# relay.net
KiCad netlist of a schematic drawn in EAGLE
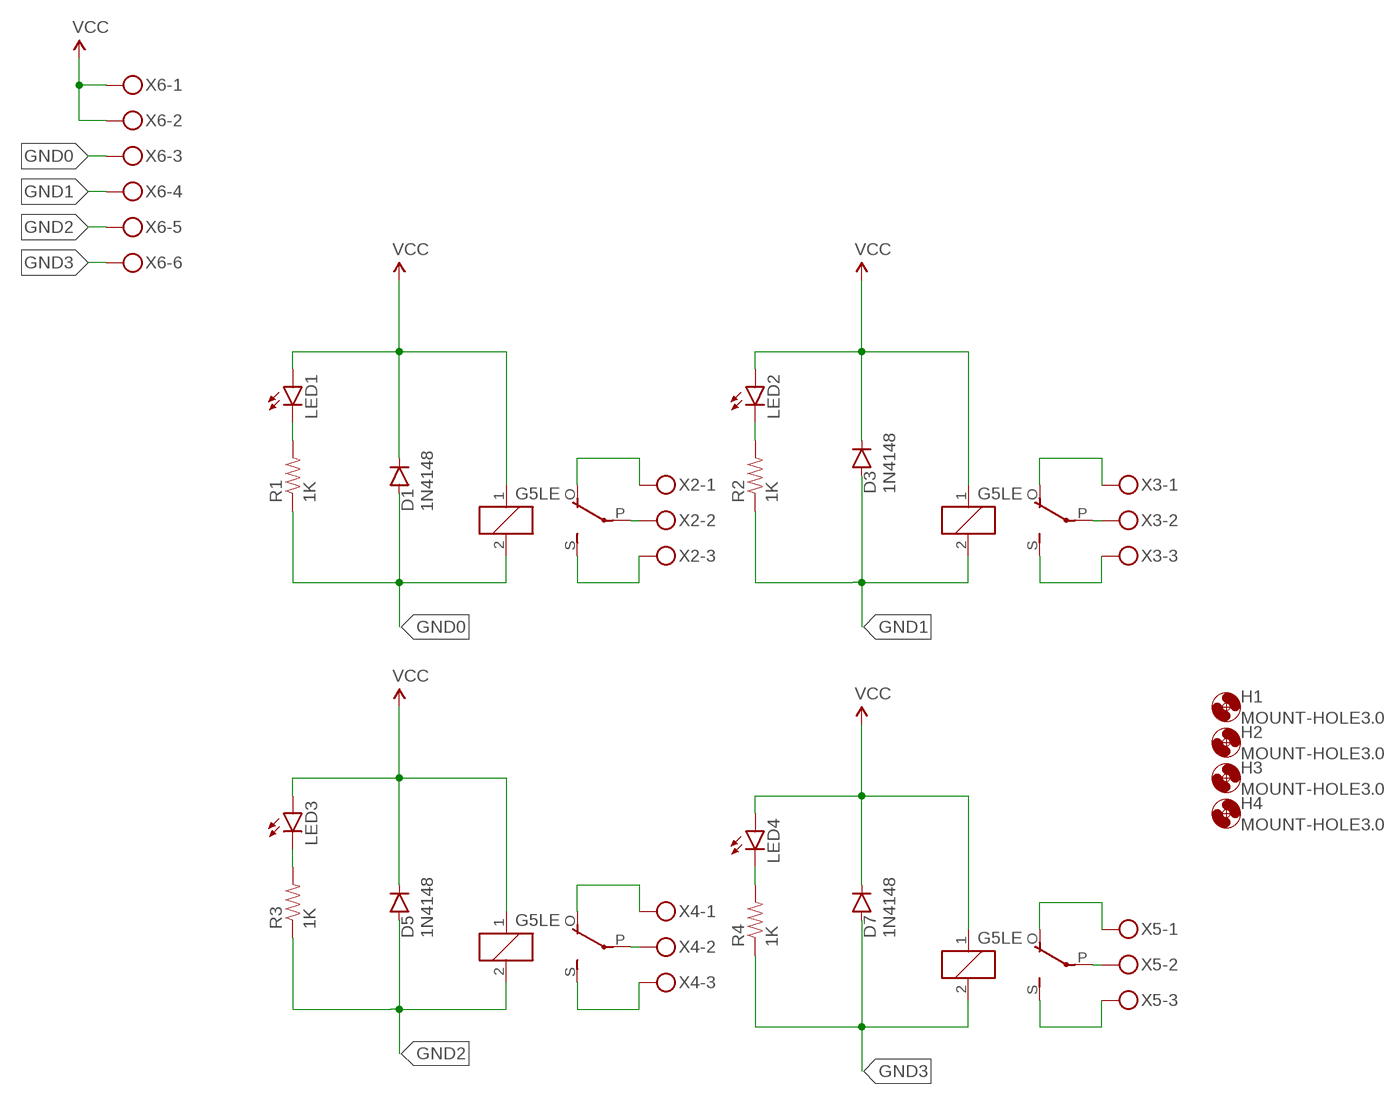
[diagram p0: schematic, sheet 1]

(export (version "E")
  (design (tool "Eeschema 10.0.6"))
  (components
    (comp (ref "D1")
      (value "1N4148")
      (footprint "eagle-import:DIODE-1N4148-KIT")
      (libsource (lib "eagle-import") (part "DIODEKIT"))
    )
    (comp (ref "D3")
      (value "1N4148")
      (footprint "eagle-import:DIODE-1N4148-KIT")
      (libsource (lib "eagle-import") (part "DIODEKIT"))
    )
    (comp (ref "D5")
      (value "1N4148")
      (footprint "eagle-import:DIODE-1N4148-KIT")
      (libsource (lib "eagle-import") (part "DIODEKIT"))
    )
    (comp (ref "D7")
      (value "1N4148")
      (footprint "eagle-import:DIODE-1N4148-KIT")
      (libsource (lib "eagle-import") (part "DIODEKIT"))
    )
    (comp (ref "H1")
      (value "MOUNT-HOLE3.0")
      (footprint "eagle-import:3,0")
      (libsource (lib "eagle-import") (part "MOUNT-HOLE3.0"))
    )
    (comp (ref "H2")
      (value "MOUNT-HOLE3.0")
      (footprint "eagle-import:3,0")
      (libsource (lib "eagle-import") (part "MOUNT-HOLE3.0"))
    )
    (comp (ref "H3")
      (value "MOUNT-HOLE3.0")
      (footprint "eagle-import:3,0")
      (libsource (lib "eagle-import") (part "MOUNT-HOLE3.0"))
    )
    (comp (ref "H4")
      (value "MOUNT-HOLE3.0")
      (footprint "eagle-import:3,0")
      (libsource (lib "eagle-import") (part "MOUNT-HOLE3.0"))
    )
    (comp (ref "K1")
      (value "G5LE")
      (footprint "eagle-import:G5LE")
      (libsource (lib "eagle-import") (part "G5LE"))
    )
    (comp (ref "K2")
      (value "G5LE")
      (footprint "eagle-import:G5LE")
      (libsource (lib "eagle-import") (part "G5LE"))
    )
    (comp (ref "K3")
      (value "G5LE")
      (footprint "eagle-import:G5LE")
      (libsource (lib "eagle-import") (part "G5LE"))
    )
    (comp (ref "K4")
      (value "G5LE")
      (footprint "eagle-import:G5LE")
      (libsource (lib "eagle-import") (part "G5LE"))
    )
    (comp (ref "LED1")
      (value "LED3MM")
      (footprint "eagle-import:LED3MM")
      (fields (field (name "PROD_ID") "DIO-09529"))
      (libsource (lib "eagle-import") (part "LED3MM"))
    )
    (comp (ref "LED2")
      (value "LED3MM")
      (footprint "eagle-import:LED3MM")
      (fields (field (name "PROD_ID") "DIO-09529"))
      (libsource (lib "eagle-import") (part "LED3MM"))
    )
    (comp (ref "LED3")
      (value "LED3MM")
      (footprint "eagle-import:LED3MM")
      (fields (field (name "PROD_ID") "DIO-09529"))
      (libsource (lib "eagle-import") (part "LED3MM"))
    )
    (comp (ref "LED4")
      (value "LED3MM")
      (footprint "eagle-import:LED3MM")
      (fields (field (name "PROD_ID") "DIO-09529"))
      (libsource (lib "eagle-import") (part "LED3MM"))
    )
    (comp (ref "R1")
      (value "1K")
      (footprint "eagle-import:AXIAL-0.3EZ")
      (libsource (lib "eagle-import") (part "1KOHM-1/4W-1%(PTH)HORIZ-KIT"))
    )
    (comp (ref "R2")
      (value "1K")
      (footprint "eagle-import:AXIAL-0.3EZ")
      (libsource (lib "eagle-import") (part "1KOHM-1/4W-1%(PTH)HORIZ-KIT"))
    )
    (comp (ref "R3")
      (value "1K")
      (footprint "eagle-import:AXIAL-0.3EZ")
      (libsource (lib "eagle-import") (part "1KOHM-1/4W-1%(PTH)HORIZ-KIT"))
    )
    (comp (ref "R4")
      (value "1K")
      (footprint "eagle-import:AXIAL-0.3EZ")
      (libsource (lib "eagle-import") (part "1KOHM-1/4W-1%(PTH)HORIZ-KIT"))
    )
    (comp (ref "X2")
      (value "MKDSN1,5/3-5,08")
      (footprint "eagle-import:MKDSN1,5_3-5,08")
      (libsource (lib "eagle-import") (part "MKDSN1,5/3-5,08"))
    )
    (comp (ref "X3")
      (value "MKDSN1,5/3-5,08")
      (footprint "eagle-import:MKDSN1,5_3-5,08")
      (libsource (lib "eagle-import") (part "MKDSN1,5/3-5,08"))
    )
    (comp (ref "X4")
      (value "MKDSN1,5/3-5,08")
      (footprint "eagle-import:MKDSN1,5_3-5,08")
      (libsource (lib "eagle-import") (part "MKDSN1,5/3-5,08"))
    )
    (comp (ref "X5")
      (value "MKDSN1,5/3-5,08")
      (footprint "eagle-import:MKDSN1,5_3-5,08")
      (libsource (lib "eagle-import") (part "MKDSN1,5/3-5,08"))
    )
    (comp (ref "X6")
      (value "MKDSN1,5/6-5,08")
      (footprint "eagle-import:MKDSN1,5_6-5,08")
      (libsource (lib "eagle-import") (part "MKDSN1,5/6-5,08"))
    )
  )
  (nets
    (net (code "1") (name "GND0") (class "Default")
      (node (ref "D1") (pin "A") (pinfunction "A_A") (pintype "passive"))
      (node (ref "K2") (pin "2") (pinfunction "2_2") (pintype "passive"))
      (node (ref "R1") (pin "P$1") (pinfunction "1_P$1") (pintype "passive"))
      (node (ref "X6") (pin "3") (pinfunction "KL_3") (pintype "passive"))
    )
    (net (code "2") (name "GND1") (class "Default")
      (node (ref "D3") (pin "A") (pinfunction "A_A") (pintype "passive"))
      (node (ref "K1") (pin "2") (pinfunction "2_2") (pintype "passive"))
      (node (ref "R2") (pin "P$1") (pinfunction "1_P$1") (pintype "passive"))
      (node (ref "X6") (pin "4") (pinfunction "KL_4") (pintype "passive"))
    )
    (net (code "3") (name "GND2") (class "Default")
      (node (ref "D5") (pin "A") (pinfunction "A_A") (pintype "passive"))
      (node (ref "K3") (pin "2") (pinfunction "2_2") (pintype "passive"))
      (node (ref "R3") (pin "P$1") (pinfunction "1_P$1") (pintype "passive"))
      (node (ref "X6") (pin "5") (pinfunction "KL_5") (pintype "passive"))
    )
    (net (code "4") (name "GND3") (class "Default")
      (node (ref "D7") (pin "A") (pinfunction "A_A") (pintype "passive"))
      (node (ref "K4") (pin "2") (pinfunction "2_2") (pintype "passive"))
      (node (ref "R4") (pin "P$1") (pinfunction "1_P$1") (pintype "passive"))
      (node (ref "X6") (pin "6") (pinfunction "KL_6") (pintype "passive"))
    )
    (net (code "5") (name "Net-(LED1-C)") (class "Default")
      (node (ref "LED1") (pin "K") (pinfunction "C_K") (pintype "passive"))
      (node (ref "R1") (pin "P$2") (pinfunction "2_P$2") (pintype "passive"))
    )
    (net (code "6") (name "Net-(LED2-C)") (class "Default")
      (node (ref "LED2") (pin "K") (pinfunction "C_K") (pintype "passive"))
      (node (ref "R2") (pin "P$2") (pinfunction "2_P$2") (pintype "passive"))
    )
    (net (code "7") (name "Net-(LED3-C)") (class "Default")
      (node (ref "LED3") (pin "K") (pinfunction "C_K") (pintype "passive"))
      (node (ref "R3") (pin "P$2") (pinfunction "2_P$2") (pintype "passive"))
    )
    (net (code "8") (name "Net-(LED4-C)") (class "Default")
      (node (ref "LED4") (pin "K") (pinfunction "C_K") (pintype "passive"))
      (node (ref "R4") (pin "P$2") (pinfunction "2_P$2") (pintype "passive"))
    )
    (net (code "9") (name "Net-(X2A-KL)") (class "Default")
      (node (ref "K2") (pin "O") (pinfunction "O_O") (pintype "passive"))
      (node (ref "X2") (pin "1") (pinfunction "KL_1") (pintype "passive"))
    )
    (net (code "10") (name "Net-(X2B-KL)") (class "Default")
      (node (ref "K2") (pin "P") (pinfunction "P_P") (pintype "passive"))
      (node (ref "X2") (pin "2") (pinfunction "KL_2") (pintype "passive"))
    )
    (net (code "11") (name "Net-(X2C-KL)") (class "Default")
      (node (ref "K2") (pin "S") (pinfunction "S_S") (pintype "passive"))
      (node (ref "X2") (pin "3") (pinfunction "KL_3") (pintype "passive"))
    )
    (net (code "12") (name "Net-(X3A-KL)") (class "Default")
      (node (ref "K1") (pin "O") (pinfunction "O_O") (pintype "passive"))
      (node (ref "X3") (pin "1") (pinfunction "KL_1") (pintype "passive"))
    )
    (net (code "13") (name "Net-(X3B-KL)") (class "Default")
      (node (ref "K1") (pin "P") (pinfunction "P_P") (pintype "passive"))
      (node (ref "X3") (pin "2") (pinfunction "KL_2") (pintype "passive"))
    )
    (net (code "14") (name "Net-(X3C-KL)") (class "Default")
      (node (ref "K1") (pin "S") (pinfunction "S_S") (pintype "passive"))
      (node (ref "X3") (pin "3") (pinfunction "KL_3") (pintype "passive"))
    )
    (net (code "15") (name "Net-(X4A-KL)") (class "Default")
      (node (ref "K3") (pin "O") (pinfunction "O_O") (pintype "passive"))
      (node (ref "X4") (pin "1") (pinfunction "KL_1") (pintype "passive"))
    )
    (net (code "16") (name "Net-(X4B-KL)") (class "Default")
      (node (ref "K3") (pin "P") (pinfunction "P_P") (pintype "passive"))
      (node (ref "X4") (pin "2") (pinfunction "KL_2") (pintype "passive"))
    )
    (net (code "17") (name "Net-(X4C-KL)") (class "Default")
      (node (ref "K3") (pin "S") (pinfunction "S_S") (pintype "passive"))
      (node (ref "X4") (pin "3") (pinfunction "KL_3") (pintype "passive"))
    )
    (net (code "18") (name "Net-(X5A-KL)") (class "Default")
      (node (ref "K4") (pin "O") (pinfunction "O_O") (pintype "passive"))
      (node (ref "X5") (pin "1") (pinfunction "KL_1") (pintype "passive"))
    )
    (net (code "19") (name "Net-(X5B-KL)") (class "Default")
      (node (ref "K4") (pin "P") (pinfunction "P_P") (pintype "passive"))
      (node (ref "X5") (pin "2") (pinfunction "KL_2") (pintype "passive"))
    )
    (net (code "20") (name "Net-(X5C-KL)") (class "Default")
      (node (ref "K4") (pin "S") (pinfunction "S_S") (pintype "passive"))
      (node (ref "X5") (pin "3") (pinfunction "KL_3") (pintype "passive"))
    )
    (net (code "21") (name "VCC") (class "Default")
      (node (ref "D1") (pin "C") (pinfunction "C_C") (pintype "passive"))
      (node (ref "D3") (pin "C") (pinfunction "C_C") (pintype "passive"))
      (node (ref "D5") (pin "C") (pinfunction "C_C") (pintype "passive"))
      (node (ref "D7") (pin "C") (pinfunction "C_C") (pintype "passive"))
      (node (ref "K1") (pin "1") (pinfunction "1_1") (pintype "passive"))
      (node (ref "K2") (pin "1") (pinfunction "1_1") (pintype "passive"))
      (node (ref "K3") (pin "1") (pinfunction "1_1") (pintype "passive"))
      (node (ref "K4") (pin "1") (pinfunction "1_1") (pintype "passive"))
      (node (ref "LED1") (pin "A") (pinfunction "A_A") (pintype "passive"))
      (node (ref "LED2") (pin "A") (pinfunction "A_A") (pintype "passive"))
      (node (ref "LED3") (pin "A") (pinfunction "A_A") (pintype "passive"))
      (node (ref "LED4") (pin "A") (pinfunction "A_A") (pintype "passive"))
      (node (ref "X6") (pin "1") (pinfunction "KL_1") (pintype "passive"))
      (node (ref "X6") (pin "2") (pinfunction "KL_2") (pintype "passive"))
    )
  )
)
